# garatea-board.net
KiCad netlist of a schematic drawn in EAGLE
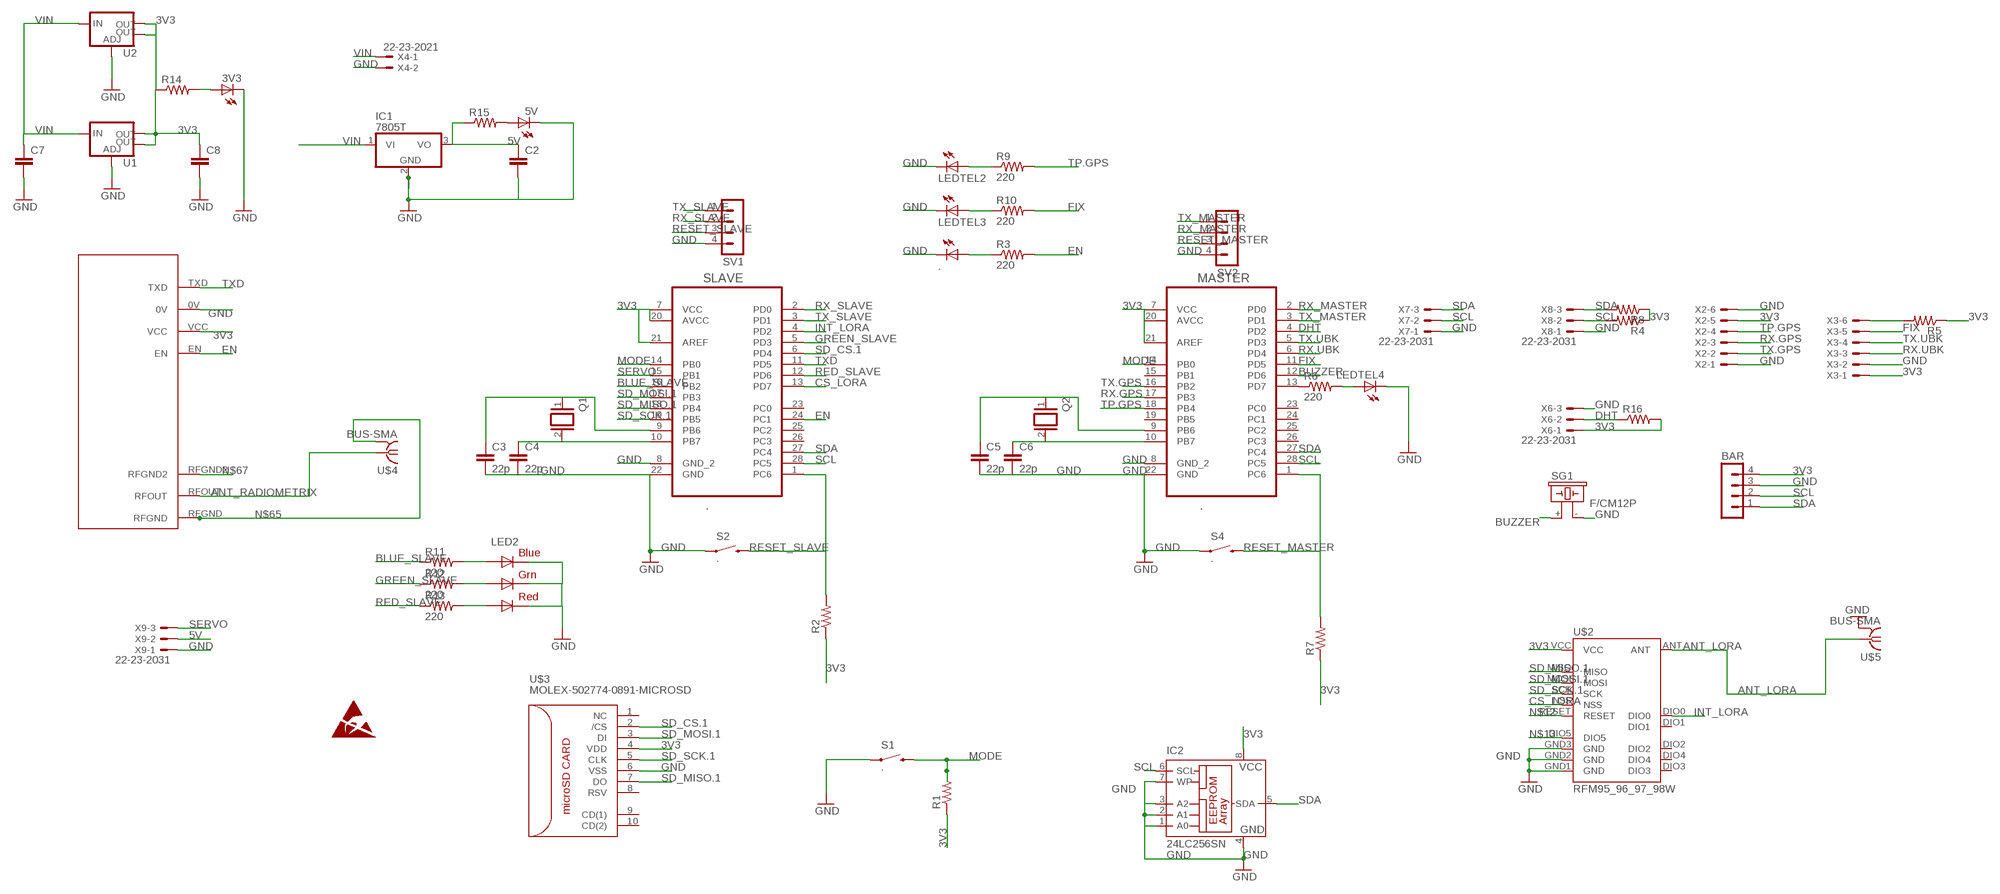
[diagram p0: schematic, sheet 1]

(export (version "E")
  (design (tool "Eeschema 10.0.6"))
  (components
    (comp (ref ".")
      (value "LEDSMT1206")
      (footprint "eagle-import:1206")
      (libsource (lib "eagle-import") (part "LEDSMT1206"))
    )
    (comp (ref "3V3")
      (value "LEDSMT1206")
      (footprint "eagle-import:1206")
      (libsource (lib "eagle-import") (part "LEDSMT1206"))
    )
    (comp (ref "5V")
      (value "LEDSMT1206")
      (footprint "eagle-import:1206")
      (libsource (lib "eagle-import") (part "LEDSMT1206"))
    )
    (comp (ref "BAR")
      (value "MA04-1")
      (footprint "eagle-import:MA04-1")
      (libsource (lib "eagle-import") (part "MA04-1"))
    )
    (comp (ref "C2")
      (value "10UF-1210-50V-20%")
      (footprint "eagle-import:1210")
      (libsource (lib "eagle-import") (part "10UF-1210-50V-20%"))
    )
    (comp (ref "C3")
      (value "22p")
      (footprint "eagle-import:1210")
      (libsource (lib "eagle-import") (part "22UF-1210-16V-20%"))
    )
    (comp (ref "C4")
      (value "22p")
      (footprint "eagle-import:1210")
      (libsource (lib "eagle-import") (part "10UF-1210-50V-20%"))
    )
    (comp (ref "C5")
      (value "22p")
      (footprint "eagle-import:1210")
      (libsource (lib "eagle-import") (part "10UF-1210-50V-20%"))
    )
    (comp (ref "C6")
      (value "22p")
      (footprint "eagle-import:1210")
      (libsource (lib "eagle-import") (part "10UF-1210-50V-20%"))
    )
    (comp (ref "C7")
      (value "10UF-1210-50V-20%")
      (footprint "eagle-import:1210")
      (libsource (lib "eagle-import") (part "10UF-1210-50V-20%"))
    )
    (comp (ref "C8")
      (value "10UF-1210-50V-20%")
      (footprint "eagle-import:1210")
      (libsource (lib "eagle-import") (part "10UF-1210-50V-20%"))
    )
    (comp (ref "IC1")
      (value "7805T")
      (footprint "eagle-import:TO220H")
      (libsource (lib "eagle-import") (part "78T05"))
    )
    (comp (ref "IC2")
      (value "24LC256SN")
      (footprint "eagle-import:SO-08")
      (fields (field (name "MF") "MICROCHIP") (field (name "MPN") "24LC256-I/SN"))
      (libsource (lib "eagle-import") (part "24SNLC256"))
    )
    (comp (ref "LED2")
      (value "RGBLED5050")
      (footprint "eagle-import:RGBLED5050")
      (libsource (lib "eagle-import") (part "RGBLED5050"))
    )
    (comp (ref "LEDTEL2")
      (value "LEDSMT1206")
      (footprint "eagle-import:1206")
      (libsource (lib "eagle-import") (part "LEDSMT1206"))
    )
    (comp (ref "LEDTEL3")
      (value "LEDSMT1206")
      (footprint "eagle-import:1206")
      (libsource (lib "eagle-import") (part "LEDSMT1206"))
    )
    (comp (ref "LEDTEL4")
      (value "LEDSMT1206")
      (footprint "eagle-import:1206")
      (libsource (lib "eagle-import") (part "LEDSMT1206"))
    )
    (comp (ref "MASTER")
      (value ".")
      (footprint "eagle-import:DIP254P762X457-28")
      (fields (field (name "MPN") "ATMEGA328P-PU"))
      (libsource (lib "eagle-import") (part "ATMEGA328P-PU"))
    )
    (comp (ref "Q1")
      (value "XTAL/S")
      (footprint "eagle-import:QS")
      (libsource (lib "eagle-import") (part "XTAL/S"))
    )
    (comp (ref "Q2")
      (value "XTAL/S")
      (footprint "eagle-import:QS")
      (libsource (lib "eagle-import") (part "XTAL/S"))
    )
    (comp (ref "R1")
      (value "R-US_M1206")
      (footprint "eagle-import:M1206")
      (libsource (lib "eagle-import") (part "R-US_M1206"))
    )
    (comp (ref "R2")
      (value "R-US_M1206")
      (footprint "eagle-import:M1206")
      (libsource (lib "eagle-import") (part "R-US_M1206"))
    )
    (comp (ref "R3")
      (value "220")
      (footprint "eagle-import:M1206")
      (libsource (lib "eagle-import") (part "R-US_M1206"))
    )
    (comp (ref "R4")
      (value "R-US_M1206")
      (footprint "eagle-import:M1206")
      (libsource (lib "eagle-import") (part "R-US_M1206"))
    )
    (comp (ref "R5")
      (value "R-US_M1206")
      (footprint "eagle-import:M1206")
      (libsource (lib "eagle-import") (part "R-US_M1206"))
    )
    (comp (ref "R6")
      (value "220")
      (footprint "eagle-import:M1206")
      (libsource (lib "eagle-import") (part "R-US_M1206"))
    )
    (comp (ref "R7")
      (value "R-US_M1206")
      (footprint "eagle-import:M1206")
      (libsource (lib "eagle-import") (part "R-US_M1206"))
    )
    (comp (ref "R8")
      (value "R-US_M1206")
      (footprint "eagle-import:M1206")
      (libsource (lib "eagle-import") (part "R-US_M1206"))
    )
    (comp (ref "R9")
      (value "220")
      (footprint "eagle-import:M1206")
      (libsource (lib "eagle-import") (part "R-US_M1206"))
    )
    (comp (ref "R10")
      (value "220")
      (footprint "eagle-import:M1206")
      (libsource (lib "eagle-import") (part "R-US_M1206"))
    )
    (comp (ref "R11")
      (value "220")
      (footprint "eagle-import:M1206")
      (libsource (lib "eagle-import") (part "R-US_M1206"))
    )
    (comp (ref "R12")
      (value "220")
      (footprint "eagle-import:M1206")
      (libsource (lib "eagle-import") (part "R-US_M1206"))
    )
    (comp (ref "R13")
      (value "220")
      (footprint "eagle-import:M1206")
      (libsource (lib "eagle-import") (part "R-US_M1206"))
    )
    (comp (ref "R14")
      (value "R-US_M1206")
      (footprint "eagle-import:M1206")
      (libsource (lib "eagle-import") (part "R-US_M1206"))
    )
    (comp (ref "R15")
      (value "R-US_M1206")
      (footprint "eagle-import:M1206")
      (libsource (lib "eagle-import") (part "R-US_M1206"))
    )
    (comp (ref "R16")
      (value "R-US_M1206")
      (footprint "eagle-import:M1206")
      (libsource (lib "eagle-import") (part "R-US_M1206"))
    )
    (comp (ref "S1")
      (value ".")
      (footprint "eagle-import:TACTILE-SWITCH-1101NE")
      (libsource (lib "eagle-import") (part "SWITCH-MOMENTARY-2SMD-1101NE"))
    )
    (comp (ref "S2")
      (value ".")
      (footprint "eagle-import:TACTILE-SWITCH-1101NE")
      (libsource (lib "eagle-import") (part "SWITCH-MOMENTARY-2SMD-1101NE"))
    )
    (comp (ref "S4")
      (value ".")
      (footprint "eagle-import:TACTILE-SWITCH-1101NE")
      (libsource (lib "eagle-import") (part "SWITCH-MOMENTARY-2SMD-1101NE"))
    )
    (comp (ref "SG1")
      (value "F/CM12P")
      (footprint "eagle-import:F_CM12P")
      (libsource (lib "eagle-import") (part "F/CM12P"))
    )
    (comp (ref "SLAVE")
      (value ".")
      (footprint "eagle-import:DIP254P762X457-28")
      (fields (field (name "MPN") "ATMEGA328P-PU"))
      (libsource (lib "eagle-import") (part "ATMEGA328P-PU"))
    )
    (comp (ref "SV1")
      (value "MA04-1")
      (footprint "eagle-import:MA04-1")
      (libsource (lib "eagle-import") (part "MA04-1"))
    )
    (comp (ref "SV2")
      (value "MA04-1")
      (footprint "eagle-import:MA04-1")
      (libsource (lib "eagle-import") (part "MA04-1"))
    )
    (comp (ref "U$1")
      (value "NTX2")
      (footprint "eagle-import:NTX2")
      (libsource (lib "eagle-import") (part "NTX2"))
    )
    (comp (ref "U$2")
      (value "RFM95_96_97_98W")
      (footprint "eagle-import:RFM95_96_97_98W")
      (libsource (lib "eagle-import") (part "RFM95_96_97_98W"))
    )
    (comp (ref "U$3")
      (value "MOLEX-502774-0891-MICROSD")
      (footprint "eagle-import:MOLEX-502774-0891-MICROSD")
      (libsource (lib "eagle-import") (part "MOLEX-502774-0891-MICROSD"))
    )
    (comp (ref "U$4")
      (value "BUS-SMA")
      (footprint "eagle-import:BUS-SMA")
      (libsource (lib "eagle-import") (part "BUS-SMA"))
    )
    (comp (ref "U$5")
      (value "BUS-SMA")
      (footprint "eagle-import:BUS-SMA")
      (libsource (lib "eagle-import") (part "BUS-SMA"))
    )
    (comp (ref "U1")
      (value "V_REG_LM1117SOT223")
      (footprint "eagle-import:SOT223")
      (libsource (lib "eagle-import") (part "V_REG_LM1117SOT223"))
    )
    (comp (ref "U2")
      (value "V_REG_LM1117SOT223")
      (footprint "eagle-import:SOT223")
      (libsource (lib "eagle-import") (part "SparkFun-PowerIC_V_REG_LM1117SOT223"))
    )
    (comp (ref "X2")
      (value "22-23-2061")
      (footprint "eagle-import:22-23-2061")
      (fields (field (name "MF") "MOLEX"))
      (libsource (lib "eagle-import") (part "22-23-2061"))
    )
    (comp (ref "X3")
      (value "22-23-2061")
      (footprint "eagle-import:22-23-2061")
      (fields (field (name "MF") "MOLEX"))
      (libsource (lib "eagle-import") (part "22-23-2061"))
    )
    (comp (ref "X4")
      (value "22-23-2021")
      (footprint "eagle-import:22-23-2021")
      (fields (field (name "MF") "MOLEX"))
      (libsource (lib "eagle-import") (part "22-23-2021"))
    )
    (comp (ref "X6")
      (value "22-23-2031")
      (footprint "eagle-import:22-23-2031")
      (fields (field (name "MF") "MOLEX"))
      (libsource (lib "eagle-import") (part "22-23-2031"))
    )
    (comp (ref "X7")
      (value "22-23-2031")
      (footprint "eagle-import:22-23-2031")
      (fields (field (name "MF") "MOLEX"))
      (libsource (lib "eagle-import") (part "22-23-2031"))
    )
    (comp (ref "X8")
      (value "22-23-2031")
      (footprint "eagle-import:22-23-2031")
      (fields (field (name "MF") "MOLEX"))
      (libsource (lib "eagle-import") (part "22-23-2031"))
    )
    (comp (ref "X9")
      (value "22-23-2031")
      (footprint "eagle-import:22-23-2031")
      (fields (field (name "MF") "MOLEX"))
      (libsource (lib "eagle-import") (part "22-23-2031"))
    )
  )
  (nets
    (net (code "1") (name "/3V3") (class "Default")
      (node (ref "BAR") (pin "4") (pinfunction "4_4") (pintype "passive"))
      (node (ref "C8") (pin "1") (pinfunction "1_1") (pintype "passive"))
      (node (ref "IC2") (pin "8") (pinfunction "VCC_8") (pintype "power_in"))
      (node (ref "MASTER") (pin "20") (pinfunction "AVCC_20") (pintype "power_in"))
      (node (ref "MASTER") (pin "21") (pinfunction "AREF_21") (pintype "input"))
      (node (ref "MASTER") (pin "7") (pinfunction "VCC_7") (pintype "power_in"))
      (node (ref "R1") (pin "1") (pinfunction "1_1") (pintype "passive"))
      (node (ref "R14") (pin "1") (pinfunction "1_1") (pintype "passive"))
      (node (ref "R16") (pin "2") (pinfunction "2_2") (pintype "passive"))
      (node (ref "R2") (pin "1") (pinfunction "1_1") (pintype "passive"))
      (node (ref "R4") (pin "1") (pinfunction "1_1") (pintype "passive"))
      (node (ref "R5") (pin "1") (pinfunction "1_1") (pintype "passive"))
      (node (ref "R7") (pin "1") (pinfunction "1_1") (pintype "passive"))
      (node (ref "R8") (pin "1") (pinfunction "1_1") (pintype "passive"))
      (node (ref "SLAVE") (pin "20") (pinfunction "AVCC_20") (pintype "power_in"))
      (node (ref "SLAVE") (pin "21") (pinfunction "AREF_21") (pintype "input"))
      (node (ref "SLAVE") (pin "7") (pinfunction "VCC_7") (pintype "power_in"))
      (node (ref "U$1") (pin "VCC") (pinfunction "VCC_VCC") (pintype "bidirectional"))
      (node (ref "U$2") (pin "VCC") (pinfunction "VCC_VCC") (pintype "bidirectional"))
      (node (ref "U$3") (pin "4") (pinfunction "VDD_4") (pintype "bidirectional"))
      (node (ref "U1") (pin "2") (pinfunction "OUT_2") (pintype "output"))
      (node (ref "U1") (pin "4") (pinfunction "OUT_4") (pintype "output"))
      (node (ref "U2") (pin "2") (pinfunction "OUT_2") (pintype "output"))
      (node (ref "U2") (pin "4") (pinfunction "OUT_4") (pintype "output"))
      (node (ref "X2") (pin "5") (pinfunction "S_5") (pintype "passive"))
      (node (ref "X3") (pin "1") (pinfunction "S_1") (pintype "passive"))
      (node (ref "X6") (pin "1") (pinfunction "S_1") (pintype "passive"))
    )
    (net (code "2") (name "/5V") (class "Default")
      (node (ref "C2") (pin "1") (pinfunction "1_1") (pintype "passive"))
      (node (ref "IC1") (pin "3") (pinfunction "VO_3") (pintype "passive"))
      (node (ref "R15") (pin "1") (pinfunction "1_1") (pintype "passive"))
      (node (ref "X9") (pin "2") (pinfunction "S_2") (pintype "passive"))
    )
    (net (code "3") (name "/ANT_LORA") (class "Default")
      (node (ref "U$2") (pin "ANT") (pinfunction "ANT_ANT") (pintype "bidirectional"))
      (node (ref "U$5") (pin "1") (pinfunction "1_1") (pintype "passive"))
    )
    (net (code "4") (name "/ANT_RADIOMETRIX") (class "Default")
      (node (ref "U$1") (pin "RFOUT") (pinfunction "RFOUT_RFOUT") (pintype "bidirectional"))
      (node (ref "U$4") (pin "1") (pinfunction "1_1") (pintype "passive"))
    )
    (net (code "5") (name "/BLUE_SLAVE") (class "Default")
      (node (ref "R11") (pin "1") (pinfunction "1_1") (pintype "passive"))
      (node (ref "SLAVE") (pin "16") (pinfunction "PB2_16") (pintype "bidirectional"))
    )
    (net (code "6") (name "/BUZZER") (class "Default")
      (node (ref "MASTER") (pin "12") (pinfunction "PD6_12") (pintype "bidirectional"))
      (node (ref "SG1") (pin "+") (pinfunction "1_+") (pintype "passive"))
    )
    (net (code "7") (name "/CS_LORA") (class "Default")
      (node (ref "SLAVE") (pin "13") (pinfunction "PD7_13") (pintype "bidirectional"))
      (node (ref "U$2") (pin "NSS") (pinfunction "NSS_NSS") (pintype "input"))
    )
    (net (code "8") (name "/DHT") (class "Default")
      (node (ref "MASTER") (pin "4") (pinfunction "PD2_4") (pintype "bidirectional"))
      (node (ref "R16") (pin "1") (pinfunction "1_1") (pintype "passive"))
      (node (ref "X6") (pin "2") (pinfunction "S_2") (pintype "passive"))
    )
    (net (code "9") (name "/EN") (class "Default")
      (node (ref "R3") (pin "2") (pinfunction "2_2") (pintype "passive"))
      (node (ref "SLAVE") (pin "24") (pinfunction "PC1_24") (pintype "bidirectional"))
      (node (ref "U$1") (pin "EN") (pinfunction "EN_EN") (pintype "bidirectional"))
    )
    (net (code "10") (name "/FIX") (class "Default")
      (node (ref "MASTER") (pin "11") (pinfunction "PD5_11") (pintype "bidirectional"))
      (node (ref "R10") (pin "2") (pinfunction "2_2") (pintype "passive"))
      (node (ref "X3") (pin "5") (pinfunction "S_5") (pintype "passive"))
    )
    (net (code "11") (name "/GREEN_SLAVE") (class "Default")
      (node (ref "R12") (pin "1") (pinfunction "1_1") (pintype "passive"))
      (node (ref "SLAVE") (pin "5") (pinfunction "PD3_5") (pintype "bidirectional"))
    )
    (net (code "12") (name "/INT_LORA") (class "Default")
      (node (ref "SLAVE") (pin "4") (pinfunction "PD2_4") (pintype "bidirectional"))
      (node (ref "U$2") (pin "DIO0") (pinfunction "DIO0_DIO0") (pintype "input"))
    )
    (net (code "13") (name "/MODE") (class "Default")
      (node (ref "MASTER") (pin "14") (pinfunction "PB0_14") (pintype "bidirectional"))
      (node (ref "R1") (pin "2") (pinfunction "2_2") (pintype "passive"))
      (node (ref "S1") (pin "2") (pinfunction "2_2") (pintype "passive"))
      (node (ref "SLAVE") (pin "14") (pinfunction "PB0_14") (pintype "bidirectional"))
    )
    (net (code "14") (name "/N$12") (class "Default")
      (node (ref "U$2") (pin "RESET") (pinfunction "RESET_RESET") (pintype "output"))
    )
    (net (code "15") (name "/N$13") (class "Default")
      (node (ref "U$2") (pin "DIO5") (pinfunction "DIO5_DIO5") (pintype "input"))
    )
    (net (code "16") (name "/N$65") (class "Default")
      (node (ref "U$1") (pin "RFGND") (pinfunction "RFGND_RFGND") (pintype "bidirectional"))
      (node (ref "U$4") (pin "2") (pinfunction "GND_2") (pintype "power_in"))
      (node (ref "U$4") (pin "3") (pinfunction "GND_3") (pintype "power_in"))
      (node (ref "U$4") (pin "4") (pinfunction "GND_4") (pintype "power_in"))
      (node (ref "U$4") (pin "5") (pinfunction "GND_5") (pintype "power_in"))
    )
    (net (code "17") (name "/N$67") (class "Default")
      (node (ref "U$1") (pin "RFGND2") (pinfunction "RFGND2_RFGND2") (pintype "bidirectional"))
    )
    (net (code "18") (name "/RED_SLAVE") (class "Default")
      (node (ref "R13") (pin "1") (pinfunction "1_1") (pintype "passive"))
      (node (ref "SLAVE") (pin "12") (pinfunction "PD6_12") (pintype "bidirectional"))
    )
    (net (code "19") (name "/RESET_MASTER") (class "Default")
      (node (ref "MASTER") (pin "1") (pinfunction "PC6_1") (pintype "bidirectional"))
      (node (ref "R7") (pin "2") (pinfunction "2_2") (pintype "passive"))
      (node (ref "S4") (pin "2") (pinfunction "2_2") (pintype "passive"))
      (node (ref "SV2") (pin "3") (pinfunction "3_3") (pintype "passive"))
    )
    (net (code "20") (name "/RESET_SLAVE") (class "Default")
      (node (ref "R2") (pin "2") (pinfunction "2_2") (pintype "passive"))
      (node (ref "S2") (pin "2") (pinfunction "2_2") (pintype "passive"))
      (node (ref "SLAVE") (pin "1") (pinfunction "PC6_1") (pintype "bidirectional"))
      (node (ref "SV1") (pin "3") (pinfunction "3_3") (pintype "passive"))
    )
    (net (code "21") (name "/RX.GPS") (class "Default")
      (node (ref "MASTER") (pin "17") (pinfunction "PB3_17") (pintype "bidirectional"))
      (node (ref "X2") (pin "3") (pinfunction "S_3") (pintype "passive"))
    )
    (net (code "22") (name "/RX.UBK") (class "Default")
      (node (ref "MASTER") (pin "6") (pinfunction "PD4_6") (pintype "bidirectional"))
      (node (ref "X3") (pin "3") (pinfunction "S_3") (pintype "passive"))
    )
    (net (code "23") (name "/RX_MASTER") (class "Default")
      (node (ref "MASTER") (pin "2") (pinfunction "PD0_2") (pintype "bidirectional"))
      (node (ref "SV2") (pin "2") (pinfunction "2_2") (pintype "passive"))
    )
    (net (code "24") (name "/RX_SLAVE") (class "Default")
      (node (ref "SLAVE") (pin "2") (pinfunction "PD0_2") (pintype "bidirectional"))
      (node (ref "SV1") (pin "2") (pinfunction "2_2") (pintype "passive"))
    )
    (net (code "25") (name "/SCL") (class "Default")
      (node (ref "BAR") (pin "2") (pinfunction "2_2") (pintype "passive"))
      (node (ref "IC2") (pin "6") (pinfunction "SCL_6") (pintype "input"))
      (node (ref "MASTER") (pin "28") (pinfunction "PC5_28") (pintype "bidirectional"))
      (node (ref "R4") (pin "2") (pinfunction "2_2") (pintype "passive"))
      (node (ref "SLAVE") (pin "28") (pinfunction "PC5_28") (pintype "bidirectional"))
      (node (ref "X7") (pin "2") (pinfunction "S_2") (pintype "passive"))
      (node (ref "X8") (pin "2") (pinfunction "S_2") (pintype "passive"))
    )
    (net (code "26") (name "/SDA") (class "Default")
      (node (ref "BAR") (pin "1") (pinfunction "1_1") (pintype "passive"))
      (node (ref "IC2") (pin "5") (pinfunction "SDA_5") (pintype "bidirectional"))
      (node (ref "MASTER") (pin "27") (pinfunction "PC4_27") (pintype "bidirectional"))
      (node (ref "R8") (pin "2") (pinfunction "2_2") (pintype "passive"))
      (node (ref "SLAVE") (pin "27") (pinfunction "PC4_27") (pintype "bidirectional"))
      (node (ref "X7") (pin "3") (pinfunction "S_3") (pintype "passive"))
      (node (ref "X8") (pin "3") (pinfunction "S_3") (pintype "passive"))
    )
    (net (code "27") (name "/SD_CS.1") (class "Default")
      (node (ref "SLAVE") (pin "6") (pinfunction "PD4_6") (pintype "bidirectional"))
      (node (ref "U$3") (pin "2") (pinfunction "/CS_2") (pintype "bidirectional"))
    )
    (net (code "28") (name "/SD_MISO.1") (class "Default")
      (node (ref "SLAVE") (pin "18") (pinfunction "PB4_18") (pintype "bidirectional"))
      (node (ref "U$2") (pin "MISO") (pinfunction "MISO_MISO") (pintype "output"))
      (node (ref "U$3") (pin "7") (pinfunction "DO_7") (pintype "bidirectional"))
    )
    (net (code "29") (name "/SD_MOSI.1") (class "Default")
      (node (ref "SLAVE") (pin "17") (pinfunction "PB3_17") (pintype "bidirectional"))
      (node (ref "U$2") (pin "MOSI") (pinfunction "MOSI_MOSI") (pintype "input"))
      (node (ref "U$3") (pin "3") (pinfunction "DI_3") (pintype "bidirectional"))
    )
    (net (code "30") (name "/SD_SCK.1") (class "Default")
      (node (ref "SLAVE") (pin "19") (pinfunction "PB5_19") (pintype "bidirectional"))
      (node (ref "U$2") (pin "SCK") (pinfunction "SCK_SCK") (pintype "input"))
      (node (ref "U$3") (pin "5") (pinfunction "CLK_5") (pintype "bidirectional"))
    )
    (net (code "31") (name "/SERVO") (class "Default")
      (node (ref "SLAVE") (pin "15") (pinfunction "PB1_15") (pintype "bidirectional"))
      (node (ref "X9") (pin "3") (pinfunction "S_3") (pintype "passive"))
    )
    (net (code "32") (name "/TP.GPS") (class "Default")
      (node (ref "MASTER") (pin "18") (pinfunction "PB4_18") (pintype "bidirectional"))
      (node (ref "R9") (pin "2") (pinfunction "2_2") (pintype "passive"))
      (node (ref "X2") (pin "4") (pinfunction "S_4") (pintype "passive"))
    )
    (net (code "33") (name "/TX.GPS") (class "Default")
      (node (ref "MASTER") (pin "16") (pinfunction "PB2_16") (pintype "bidirectional"))
      (node (ref "X2") (pin "2") (pinfunction "S_2") (pintype "passive"))
    )
    (net (code "34") (name "/TX.UBK") (class "Default")
      (node (ref "MASTER") (pin "5") (pinfunction "PD3_5") (pintype "bidirectional"))
      (node (ref "X3") (pin "4") (pinfunction "S_4") (pintype "passive"))
    )
    (net (code "35") (name "/TXD") (class "Default")
      (node (ref "SLAVE") (pin "11") (pinfunction "PD5_11") (pintype "bidirectional"))
      (node (ref "U$1") (pin "TXD") (pinfunction "TXD_TXD") (pintype "bidirectional"))
    )
    (net (code "36") (name "/TX_MASTER") (class "Default")
      (node (ref "MASTER") (pin "3") (pinfunction "PD1_3") (pintype "bidirectional"))
      (node (ref "SV2") (pin "1") (pinfunction "1_1") (pintype "passive"))
    )
    (net (code "37") (name "/TX_SLAVE") (class "Default")
      (node (ref "SLAVE") (pin "3") (pinfunction "PD1_3") (pintype "bidirectional"))
      (node (ref "SV1") (pin "1") (pinfunction "1_1") (pintype "passive"))
    )
    (net (code "38") (name "/VIN") (class "Default")
      (node (ref "C7") (pin "1") (pinfunction "1_1") (pintype "passive"))
      (node (ref "IC1") (pin "1") (pinfunction "VI_1") (pintype "input"))
      (node (ref "U1") (pin "3") (pinfunction "IN_3") (pintype "input"))
      (node (ref "U2") (pin "3") (pinfunction "IN_3") (pintype "input"))
      (node (ref "X4") (pin "1") (pinfunction "S_1") (pintype "passive"))
    )
    (net (code "39") (name "GND") (class "Default")
      (node (ref ".") (pin "C") (pinfunction "C_C") (pintype "passive"))
      (node (ref "3V3") (pin "C") (pinfunction "C_C") (pintype "passive"))
      (node (ref "5V") (pin "C") (pinfunction "C_C") (pintype "passive"))
      (node (ref "BAR") (pin "3") (pinfunction "3_3") (pintype "passive"))
      (node (ref "C2") (pin "2") (pinfunction "2_2") (pintype "passive"))
      (node (ref "C3") (pin "2") (pinfunction "2_2") (pintype "passive"))
      (node (ref "C4") (pin "2") (pinfunction "2_2") (pintype "passive"))
      (node (ref "C5") (pin "2") (pinfunction "2_2") (pintype "passive"))
      (node (ref "C6") (pin "2") (pinfunction "2_2") (pintype "passive"))
      (node (ref "C7") (pin "2") (pinfunction "2_2") (pintype "passive"))
      (node (ref "C8") (pin "2") (pinfunction "2_2") (pintype "passive"))
      (node (ref "IC1") (pin "2") (pinfunction "GND_2") (pintype "passive"))
      (node (ref "IC2") (pin "1") (pinfunction "A0_1") (pintype "input"))
      (node (ref "IC2") (pin "2") (pinfunction "A1_2") (pintype "input"))
      (node (ref "IC2") (pin "3") (pinfunction "A2_3") (pintype "input"))
      (node (ref "IC2") (pin "4") (pinfunction "GND_4") (pintype "power_in"))
      (node (ref "IC2") (pin "7") (pinfunction "WP_7") (pintype "input"))
      (node (ref "LED2") (pin "4") (pinfunction "BLUE_C_4") (pintype "bidirectional"))
      (node (ref "LED2") (pin "5") (pinfunction "RED_C_5") (pintype "bidirectional"))
      (node (ref "LED2") (pin "6") (pinfunction "GREEN_C_6") (pintype "bidirectional"))
      (node (ref "LEDTEL2") (pin "C") (pinfunction "C_C") (pintype "passive"))
      (node (ref "LEDTEL3") (pin "C") (pinfunction "C_C") (pintype "passive"))
      (node (ref "LEDTEL4") (pin "C") (pinfunction "C_C") (pintype "passive"))
      (node (ref "MASTER") (pin "22") (pinfunction "GND_22") (pintype "passive"))
      (node (ref "MASTER") (pin "8") (pinfunction "GND_2_8") (pintype "passive"))
      (node (ref "S1") (pin "1") (pinfunction "1_1") (pintype "passive"))
      (node (ref "S2") (pin "1") (pinfunction "1_1") (pintype "passive"))
      (node (ref "S4") (pin "1") (pinfunction "1_1") (pintype "passive"))
      (node (ref "SG1") (pin "-") (pinfunction "2_-") (pintype "passive"))
      (node (ref "SLAVE") (pin "22") (pinfunction "GND_22") (pintype "passive"))
      (node (ref "SLAVE") (pin "8") (pinfunction "GND_2_8") (pintype "passive"))
      (node (ref "SV1") (pin "4") (pinfunction "4_4") (pintype "passive"))
      (node (ref "SV2") (pin "4") (pinfunction "4_4") (pintype "passive"))
      (node (ref "U$1") (pin "0V") (pinfunction "0V_0V") (pintype "bidirectional"))
      (node (ref "U$2") (pin "GND1") (pinfunction "GND_GND1") (pintype "power_in"))
      (node (ref "U$2") (pin "GND2") (pinfunction "GND_GND2") (pintype "power_in"))
      (node (ref "U$2") (pin "GND3") (pinfunction "GND_GND3") (pintype "power_in"))
      (node (ref "U$3") (pin "6") (pinfunction "VSS_6") (pintype "bidirectional"))
      (node (ref "U$5") (pin "2") (pinfunction "GND_2") (pintype "power_in"))
      (node (ref "U$5") (pin "3") (pinfunction "GND_3") (pintype "power_in"))
      (node (ref "U$5") (pin "4") (pinfunction "GND_4") (pintype "power_in"))
      (node (ref "U$5") (pin "5") (pinfunction "GND_5") (pintype "power_in"))
      (node (ref "U1") (pin "1") (pinfunction "ADJ_1") (pintype "input"))
      (node (ref "U2") (pin "1") (pinfunction "ADJ_1") (pintype "input"))
      (node (ref "X2") (pin "1") (pinfunction "S_1") (pintype "passive"))
      (node (ref "X2") (pin "6") (pinfunction "S_6") (pintype "passive"))
      (node (ref "X3") (pin "2") (pinfunction "S_2") (pintype "passive"))
      (node (ref "X4") (pin "2") (pinfunction "S_2") (pintype "passive"))
      (node (ref "X6") (pin "3") (pinfunction "S_3") (pintype "passive"))
      (node (ref "X7") (pin "1") (pinfunction "S_1") (pintype "passive"))
      (node (ref "X8") (pin "1") (pinfunction "S_1") (pintype "passive"))
      (node (ref "X9") (pin "1") (pinfunction "S_1") (pintype "passive"))
    )
    (net (code "40") (name "Net-(.-PadA)") (class "Default")
      (node (ref ".") (pin "A") (pinfunction "A_A") (pintype "passive"))
      (node (ref "R3") (pin "1") (pinfunction "1_1") (pintype "passive"))
    )
    (net (code "41") (name "Net-(3V3-PadA)") (class "Default")
      (node (ref "3V3") (pin "A") (pinfunction "A_A") (pintype "passive"))
      (node (ref "R14") (pin "2") (pinfunction "2_2") (pintype "passive"))
    )
    (net (code "42") (name "Net-(5V-PadA)") (class "Default")
      (node (ref "5V") (pin "A") (pinfunction "A_A") (pintype "passive"))
      (node (ref "R15") (pin "2") (pinfunction "2_2") (pintype "passive"))
    )
    (net (code "43") (name "Net-(LED2-BLUE_A)") (class "Default")
      (node (ref "LED2") (pin "3") (pinfunction "BLUE_A_3") (pintype "bidirectional"))
      (node (ref "R11") (pin "2") (pinfunction "2_2") (pintype "passive"))
    )
    (net (code "44") (name "Net-(LED2-GREEN_A)") (class "Default")
      (node (ref "LED2") (pin "1") (pinfunction "GREEN_A_1") (pintype "bidirectional"))
      (node (ref "R12") (pin "2") (pinfunction "2_2") (pintype "passive"))
    )
    (net (code "45") (name "Net-(LED2-RED_A)") (class "Default")
      (node (ref "LED2") (pin "2") (pinfunction "RED_A_2") (pintype "bidirectional"))
      (node (ref "R13") (pin "2") (pinfunction "2_2") (pintype "passive"))
    )
    (net (code "46") (name "Net-(LEDTEL2-PadA)") (class "Default")
      (node (ref "LEDTEL2") (pin "A") (pinfunction "A_A") (pintype "passive"))
      (node (ref "R9") (pin "1") (pinfunction "1_1") (pintype "passive"))
    )
    (net (code "47") (name "Net-(LEDTEL3-PadA)") (class "Default")
      (node (ref "LEDTEL3") (pin "A") (pinfunction "A_A") (pintype "passive"))
      (node (ref "R10") (pin "1") (pinfunction "1_1") (pintype "passive"))
    )
    (net (code "48") (name "Net-(LEDTEL4-PadA)") (class "Default")
      (node (ref "LEDTEL4") (pin "A") (pinfunction "A_A") (pintype "passive"))
      (node (ref "R6") (pin "2") (pinfunction "2_2") (pintype "passive"))
    )
    (net (code "49") (name "Net-(MASTER-PB6)") (class "Default")
      (node (ref "C5") (pin "1") (pinfunction "1_1") (pintype "passive"))
      (node (ref "MASTER") (pin "9") (pinfunction "PB6_9") (pintype "bidirectional"))
      (node (ref "Q2") (pin "1") (pinfunction "1_1") (pintype "passive"))
    )
    (net (code "50") (name "Net-(MASTER-PB7)") (class "Default")
      (node (ref "C6") (pin "1") (pinfunction "1_1") (pintype "passive"))
      (node (ref "MASTER") (pin "10") (pinfunction "PB7_10") (pintype "bidirectional"))
      (node (ref "Q2") (pin "2") (pinfunction "2_2") (pintype "passive"))
    )
    (net (code "51") (name "Net-(MASTER-PD7)") (class "Default")
      (node (ref "MASTER") (pin "13") (pinfunction "PD7_13") (pintype "bidirectional"))
      (node (ref "R6") (pin "1") (pinfunction "1_1") (pintype "passive"))
    )
    (net (code "52") (name "Net-(SLAVE-PB6)") (class "Default")
      (node (ref "C3") (pin "1") (pinfunction "1_1") (pintype "passive"))
      (node (ref "Q1") (pin "1") (pinfunction "1_1") (pintype "passive"))
      (node (ref "SLAVE") (pin "9") (pinfunction "PB6_9") (pintype "bidirectional"))
    )
    (net (code "53") (name "Net-(SLAVE-PB7)") (class "Default")
      (node (ref "C4") (pin "1") (pinfunction "1_1") (pintype "passive"))
      (node (ref "Q1") (pin "2") (pinfunction "2_2") (pintype "passive"))
      (node (ref "SLAVE") (pin "10") (pinfunction "PB7_10") (pintype "bidirectional"))
    )
    (net (code "54") (name "Net-(X3F-S)") (class "Default")
      (node (ref "R5") (pin "2") (pinfunction "2_2") (pintype "passive"))
      (node (ref "X3") (pin "6") (pinfunction "S_6") (pintype "passive"))
    )
    (net (code "55") (name "unconnected-(MASTER-PB1-Pad15)") (class "Default")
      (node (ref "MASTER") (pin "15") (pinfunction "PB1_15") (pintype "bidirectional"))
    )
    (net (code "56") (name "unconnected-(MASTER-PB5-Pad19)") (class "Default")
      (node (ref "MASTER") (pin "19") (pinfunction "PB5_19") (pintype "bidirectional"))
    )
    (net (code "57") (name "unconnected-(MASTER-PC0-Pad23)") (class "Default")
      (node (ref "MASTER") (pin "23") (pinfunction "PC0_23") (pintype "bidirectional"))
    )
    (net (code "58") (name "unconnected-(MASTER-PC1-Pad24)") (class "Default")
      (node (ref "MASTER") (pin "24") (pinfunction "PC1_24") (pintype "bidirectional"))
    )
    (net (code "59") (name "unconnected-(MASTER-PC2-Pad25)") (class "Default")
      (node (ref "MASTER") (pin "25") (pinfunction "PC2_25") (pintype "bidirectional"))
    )
    (net (code "60") (name "unconnected-(MASTER-PC3-Pad26)") (class "Default")
      (node (ref "MASTER") (pin "26") (pinfunction "PC3_26") (pintype "bidirectional"))
    )
    (net (code "61") (name "unconnected-(SLAVE-PC0-Pad23)") (class "Default")
      (node (ref "SLAVE") (pin "23") (pinfunction "PC0_23") (pintype "bidirectional"))
    )
    (net (code "62") (name "unconnected-(SLAVE-PC2-Pad25)") (class "Default")
      (node (ref "SLAVE") (pin "25") (pinfunction "PC2_25") (pintype "bidirectional"))
    )
    (net (code "63") (name "unconnected-(SLAVE-PC3-Pad26)") (class "Default")
      (node (ref "SLAVE") (pin "26") (pinfunction "PC3_26") (pintype "bidirectional"))
    )
    (net (code "64") (name "unconnected-(U$2-PadDIO1)") (class "Default")
      (node (ref "U$2") (pin "DIO1") (pinfunction "DIO1_DIO1") (pintype "input"))
    )
    (net (code "65") (name "unconnected-(U$2-PadDIO2)") (class "Default")
      (node (ref "U$2") (pin "DIO2") (pinfunction "DIO2_DIO2") (pintype "bidirectional"))
    )
    (net (code "66") (name "unconnected-(U$2-PadDIO3)") (class "Default")
      (node (ref "U$2") (pin "DIO3") (pinfunction "DIO3_DIO3") (pintype "bidirectional"))
    )
    (net (code "67") (name "unconnected-(U$2-PadDIO4)") (class "Default")
      (node (ref "U$2") (pin "DIO4") (pinfunction "DIO4_DIO4") (pintype "bidirectional"))
    )
    (net (code "68") (name "unconnected-(U$3-CD(1)-Pad9)") (class "Default")
      (node (ref "U$3") (pin "9") (pinfunction "CD(1)_9") (pintype "bidirectional"))
    )
    (net (code "69") (name "unconnected-(U$3-CD(2)-Pad10)") (class "Default")
      (node (ref "U$3") (pin "10") (pinfunction "CD(2)_10") (pintype "bidirectional"))
    )
    (net (code "70") (name "unconnected-(U$3-NC-Pad1)") (class "Default")
      (node (ref "U$3") (pin "1") (pinfunction "NC_1") (pintype "bidirectional"))
    )
    (net (code "71") (name "unconnected-(U$3-RSV-Pad8)") (class "Default")
      (node (ref "U$3") (pin "8") (pinfunction "RSV_8") (pintype "bidirectional"))
    )
  )
)
